# schema_carte_mere.net
KiCad netlist of a schematic drawn in EAGLE
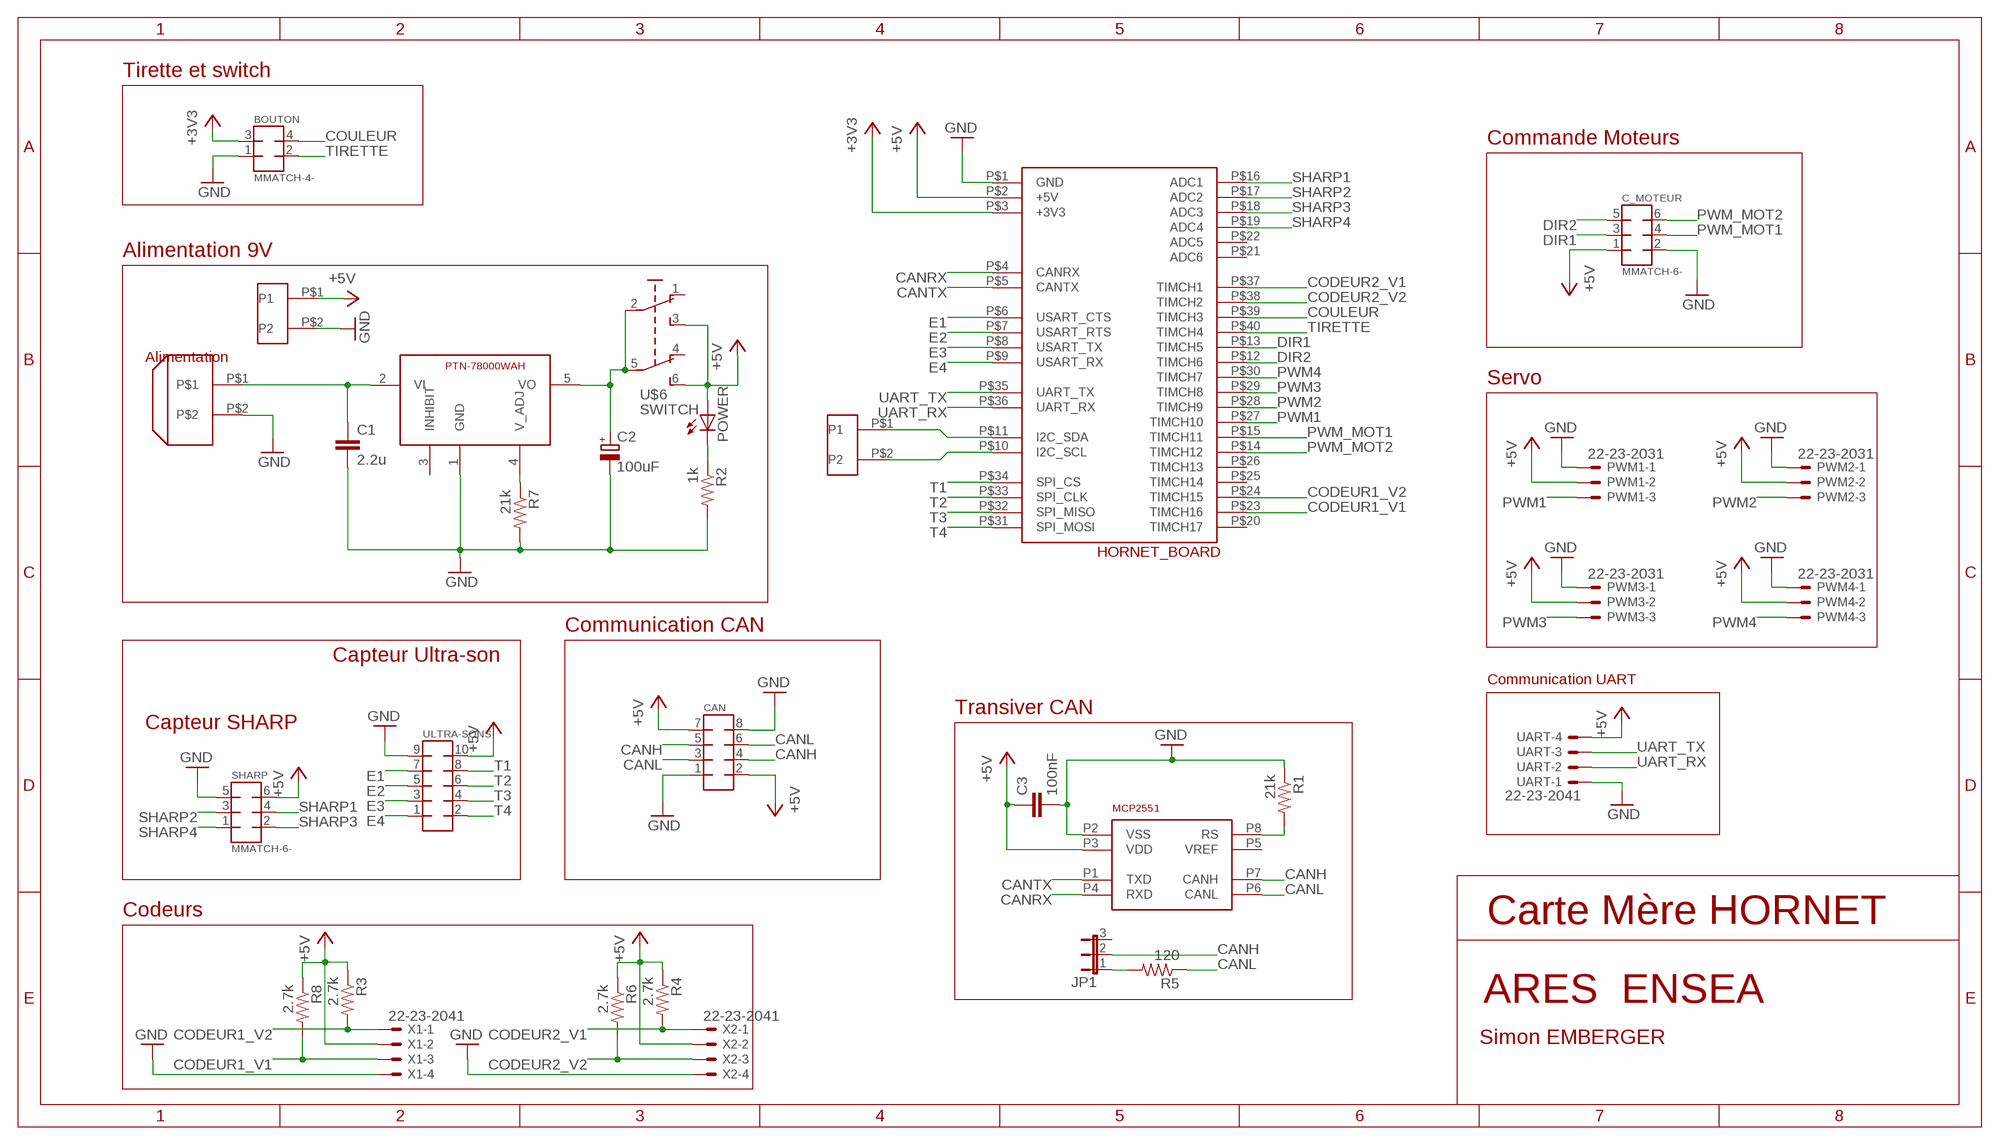
[diagram p0: schematic, sheet 1]

(export (version "E")
  (design (tool "Eeschema 10.0.6"))
  (components
    (comp (ref "ALIM")
      (value "PM5.08_2")
      (footprint "eagle-import:PM5.08_2")
      (libsource (lib "eagle-import") (part "PM5.08_2"))
    )
    (comp (ref "BOUTON")
      (value "MMATCH-4-")
      (footprint "eagle-import:AMP-215079-4")
      (libsource (lib "eagle-import") (part "MMATCH-4-"))
    )
    (comp (ref "C1")
      (value "2.2u")
      (footprint "eagle-import:C1210")
      (libsource (lib "eagle-import") (part "C-EUC1210"))
    )
    (comp (ref "C2")
      (value "100uF")
      (footprint "eagle-import:153CLV-0807")
      (libsource (lib "eagle-import") (part "CPOL-EU153CLV-0807"))
    )
    (comp (ref "C3")
      (value "100nF")
      (footprint "eagle-import:C0805")
      (libsource (lib "eagle-import") (part "C-EUC0805"))
    )
    (comp (ref "CAN")
      (value "MMATCH-8-PTH")
      (footprint "eagle-import:AMP-215079-8")
      (libsource (lib "eagle-import") (part "MMATCH-8-PTH"))
    )
    (comp (ref "C_MOTEUR")
      (value "MMATCH-6-")
      (footprint "eagle-import:AMP-215079-6")
      (libsource (lib "eagle-import") (part "MMATCH-6-"))
    )
    (comp (ref "JP1")
      (value "JP2W")
      (footprint "eagle-import:JP2W")
      (libsource (lib "eagle-import") (part "JP2W"))
    )
    (comp (ref "PIN_ALIM")
      (value "2_PIN")
      (footprint "eagle-import:2_PIN")
      (libsource (lib "eagle-import") (part "2_PIN"))
    )
    (comp (ref "POWER")
      (value "LEDCHIPLED_0805")
      (footprint "eagle-import:CHIPLED_0805")
      (libsource (lib "eagle-import") (part "LEDCHIPLED_0805"))
    )
    (comp (ref "PWM1")
      (value "22-23-2031")
      (footprint "eagle-import:22-23-2031")
      (fields (field (name "MF") "MOLEX"))
      (libsource (lib "eagle-import") (part "22-23-2031"))
    )
    (comp (ref "PWM2")
      (value "22-23-2031")
      (footprint "eagle-import:22-23-2031")
      (fields (field (name "MF") "MOLEX"))
      (libsource (lib "eagle-import") (part "22-23-2031"))
    )
    (comp (ref "PWM3")
      (value "22-23-2031")
      (footprint "eagle-import:22-23-2031")
      (fields (field (name "MF") "MOLEX"))
      (libsource (lib "eagle-import") (part "22-23-2031"))
    )
    (comp (ref "PWM4")
      (value "22-23-2031")
      (footprint "eagle-import:22-23-2031")
      (fields (field (name "MF") "MOLEX"))
      (libsource (lib "eagle-import") (part "22-23-2031"))
    )
    (comp (ref "R1")
      (value "21k")
      (footprint "eagle-import:M0805")
      (libsource (lib "eagle-import") (part "R-US_M0805"))
    )
    (comp (ref "R2")
      (value "1k")
      (footprint "eagle-import:M0805")
      (libsource (lib "eagle-import") (part "R-US_M0805"))
    )
    (comp (ref "R3")
      (value "2.7k")
      (footprint "eagle-import:M0805")
      (libsource (lib "eagle-import") (part "R-US_M0805"))
    )
    (comp (ref "R4")
      (value "2.7k")
      (footprint "eagle-import:M0805")
      (libsource (lib "eagle-import") (part "R-US_M0805"))
    )
    (comp (ref "R5")
      (value "120")
      (footprint "eagle-import:M0805")
      (libsource (lib "eagle-import") (part "R-US_M0805"))
    )
    (comp (ref "R6")
      (value "2.7k")
      (footprint "eagle-import:M0805")
      (libsource (lib "eagle-import") (part "R-US_M0805"))
    )
    (comp (ref "R7")
      (value "21k")
      (footprint "eagle-import:M0805")
      (libsource (lib "eagle-import") (part "R-US_M0805"))
    )
    (comp (ref "R8")
      (value "2.7k")
      (footprint "eagle-import:M0805")
      (libsource (lib "eagle-import") (part "R-US_M0805"))
    )
    (comp (ref "SHARP")
      (value "MMATCH-6-")
      (footprint "eagle-import:AMP-215079-6")
      (libsource (lib "eagle-import") (part "MMATCH-6-"))
    )
    (comp (ref "U$1")
      (value "HORNET_BOARD")
      (footprint "eagle-import:HORNET_EXT_20")
      (libsource (lib "eagle-import") (part "HORNET_BOARD"))
    )
    (comp (ref "U$2")
      (value "MCP2551")
      (footprint "eagle-import:SOIC_8")
      (libsource (lib "eagle-import") (part "MCP2551"))
    )
    (comp (ref "U$3")
      (value "2_PIN")
      (footprint "eagle-import:2_PIN")
      (libsource (lib "eagle-import") (part "2_PIN"))
    )
    (comp (ref "U$6")
      (value "SWITCH")
      (footprint "eagle-import:SWITCH")
      (libsource (lib "eagle-import") (part "SWITCH"))
    )
    (comp (ref "U$18")
      (value "PTN-78000WAH")
      (footprint "eagle-import:PCK-PTN-78000WAH")
      (libsource (lib "eagle-import") (part "PTN-78000WAH"))
    )
    (comp (ref "UART")
      (value "22-23-2041")
      (footprint "eagle-import:22-23-2041")
      (fields (field (name "MF") "MOLEX"))
      (libsource (lib "eagle-import") (part "22-23-2041"))
    )
    (comp (ref "ULTRA-SONS")
      (value "MMATCH-10-PTH")
      (footprint "eagle-import:AMP-215079-10")
      (libsource (lib "eagle-import") (part "MMATCH-10-PTH"))
    )
    (comp (ref "X1")
      (value "22-23-2041")
      (footprint "eagle-import:22-23-2041")
      (fields (field (name "MF") "MOLEX"))
      (libsource (lib "eagle-import") (part "22-23-2041"))
    )
    (comp (ref "X2")
      (value "22-23-2041")
      (footprint "eagle-import:22-23-2041")
      (fields (field (name "MF") "MOLEX"))
      (libsource (lib "eagle-import") (part "22-23-2041"))
    )
  )
  (nets
    (net (code "1") (name "+3V3") (class "Default")
      (node (ref "BOUTON") (pin "3") (pinfunction "7_3") (pintype "bidirectional"))
      (node (ref "U$1") (pin "P$3") (pinfunction "+3V3_P$3") (pintype "bidirectional"))
    )
    (net (code "2") (name "+5V") (class "Default")
      (node (ref "C3") (pin "1") (pinfunction "1_1") (pintype "passive"))
      (node (ref "CAN") (pin "2") (pinfunction "2_2") (pintype "bidirectional"))
      (node (ref "CAN") (pin "7") (pinfunction "7_7") (pintype "bidirectional"))
      (node (ref "C_MOTEUR") (pin "1") (pinfunction "3_1") (pintype "bidirectional"))
      (node (ref "PIN_ALIM") (pin "P$1") (pinfunction "P1_P$1") (pintype "bidirectional"))
      (node (ref "POWER") (pin "A") (pinfunction "A_A") (pintype "passive"))
      (node (ref "PWM1") (pin "2") (pinfunction "S_2") (pintype "passive"))
      (node (ref "PWM2") (pin "2") (pinfunction "S_2") (pintype "passive"))
      (node (ref "PWM3") (pin "2") (pinfunction "S_2") (pintype "passive"))
      (node (ref "PWM4") (pin "2") (pinfunction "S_2") (pintype "passive"))
      (node (ref "R3") (pin "1") (pinfunction "1_1") (pintype "passive"))
      (node (ref "R4") (pin "1") (pinfunction "1_1") (pintype "passive"))
      (node (ref "R6") (pin "1") (pinfunction "1_1") (pintype "passive"))
      (node (ref "R8") (pin "1") (pinfunction "1_1") (pintype "passive"))
      (node (ref "SHARP") (pin "6") (pinfunction "8_6") (pintype "bidirectional"))
      (node (ref "U$1") (pin "P$2") (pinfunction "+5V_P$2") (pintype "bidirectional"))
      (node (ref "U$2") (pin "P3") (pinfunction "VDD_P3") (pintype "bidirectional"))
      (node (ref "U$6") (pin "3") (pinfunction "S_3") (pintype "passive"))
      (node (ref "U$6") (pin "6") (pinfunction "S1_6") (pintype "passive"))
      (node (ref "UART") (pin "4") (pinfunction "S_4") (pintype "passive"))
      (node (ref "ULTRA-SONS") (pin "10") (pinfunction "10_10") (pintype "bidirectional"))
      (node (ref "X1") (pin "2") (pinfunction "S_2") (pintype "passive"))
      (node (ref "X2") (pin "2") (pinfunction "S_2") (pintype "passive"))
    )
    (net (code "3") (name "/CANH") (class "Default")
      (node (ref "CAN") (pin "4") (pinfunction "4_4") (pintype "bidirectional"))
      (node (ref "CAN") (pin "5") (pinfunction "5_5") (pintype "bidirectional"))
      (node (ref "JP1") (pin "2") (pinfunction "2_2") (pintype "passive"))
      (node (ref "U$2") (pin "P7") (pinfunction "CANH_P7") (pintype "bidirectional"))
    )
    (net (code "4") (name "/CANL") (class "Default")
      (node (ref "CAN") (pin "3") (pinfunction "3_3") (pintype "bidirectional"))
      (node (ref "CAN") (pin "6") (pinfunction "6_6") (pintype "bidirectional"))
      (node (ref "R5") (pin "1") (pinfunction "1_1") (pintype "passive"))
      (node (ref "U$2") (pin "P6") (pinfunction "CANL_P6") (pintype "bidirectional"))
    )
    (net (code "5") (name "/CANRX") (class "Default")
      (node (ref "U$1") (pin "P$4") (pinfunction "CANRX_P$4") (pintype "bidirectional"))
      (node (ref "U$2") (pin "P4") (pinfunction "RXD_P4") (pintype "bidirectional"))
    )
    (net (code "6") (name "/CANTX") (class "Default")
      (node (ref "U$1") (pin "P$5") (pinfunction "CANTX_P$5") (pintype "bidirectional"))
      (node (ref "U$2") (pin "P1") (pinfunction "TXD_P1") (pintype "bidirectional"))
    )
    (net (code "7") (name "/CODEUR1_V1") (class "Default")
      (node (ref "R8") (pin "2") (pinfunction "2_2") (pintype "passive"))
      (node (ref "U$1") (pin "P$23") (pinfunction "TIMCH16_P$23") (pintype "bidirectional"))
      (node (ref "X1") (pin "3") (pinfunction "S_3") (pintype "passive"))
    )
    (net (code "8") (name "/CODEUR1_V2") (class "Default")
      (node (ref "R3") (pin "2") (pinfunction "2_2") (pintype "passive"))
      (node (ref "U$1") (pin "P$24") (pinfunction "TIMCH15_P$24") (pintype "bidirectional"))
      (node (ref "X1") (pin "1") (pinfunction "S_1") (pintype "passive"))
    )
    (net (code "9") (name "/CODEUR2_V1") (class "Default")
      (node (ref "R4") (pin "2") (pinfunction "2_2") (pintype "passive"))
      (node (ref "U$1") (pin "P$37") (pinfunction "TIMCH1_P$37") (pintype "bidirectional"))
      (node (ref "X2") (pin "1") (pinfunction "S_1") (pintype "passive"))
    )
    (net (code "10") (name "/CODEUR2_V2") (class "Default")
      (node (ref "R6") (pin "2") (pinfunction "2_2") (pintype "passive"))
      (node (ref "U$1") (pin "P$38") (pinfunction "TIMCH2_P$38") (pintype "bidirectional"))
      (node (ref "X2") (pin "3") (pinfunction "S_3") (pintype "passive"))
    )
    (net (code "11") (name "/COULEUR") (class "Default")
      (node (ref "BOUTON") (pin "4") (pinfunction "8_4") (pintype "bidirectional"))
      (node (ref "U$1") (pin "P$39") (pinfunction "TIMCH3_P$39") (pintype "bidirectional"))
    )
    (net (code "12") (name "/DIR1") (class "Default")
      (node (ref "C_MOTEUR") (pin "3") (pinfunction "5_3") (pintype "bidirectional"))
      (node (ref "U$1") (pin "P$13") (pinfunction "TIMCH5_P$13") (pintype "bidirectional"))
    )
    (net (code "13") (name "/DIR2") (class "Default")
      (node (ref "C_MOTEUR") (pin "5") (pinfunction "7_5") (pintype "bidirectional"))
      (node (ref "U$1") (pin "P$12") (pinfunction "TIMCH6_P$12") (pintype "bidirectional"))
    )
    (net (code "14") (name "/E1") (class "Default")
      (node (ref "U$1") (pin "P$6") (pinfunction "USART_CTS_P$6") (pintype "bidirectional"))
      (node (ref "ULTRA-SONS") (pin "7") (pinfunction "7_7") (pintype "bidirectional"))
    )
    (net (code "15") (name "/E2") (class "Default")
      (node (ref "U$1") (pin "P$7") (pinfunction "USART_RTS_P$7") (pintype "bidirectional"))
      (node (ref "ULTRA-SONS") (pin "5") (pinfunction "5_5") (pintype "bidirectional"))
    )
    (net (code "16") (name "/E3") (class "Default")
      (node (ref "U$1") (pin "P$8") (pinfunction "USART_TX_P$8") (pintype "bidirectional"))
      (node (ref "ULTRA-SONS") (pin "3") (pinfunction "3_3") (pintype "bidirectional"))
    )
    (net (code "17") (name "/E4") (class "Default")
      (node (ref "U$1") (pin "P$9") (pinfunction "USART_RX_P$9") (pintype "bidirectional"))
      (node (ref "ULTRA-SONS") (pin "1") (pinfunction "1_1") (pintype "bidirectional"))
    )
    (net (code "18") (name "/PWM1") (class "Default")
      (node (ref "PWM1") (pin "3") (pinfunction "S_3") (pintype "passive"))
      (node (ref "U$1") (pin "P$27") (pinfunction "TIMCH10_P$27") (pintype "bidirectional"))
    )
    (net (code "19") (name "/PWM2") (class "Default")
      (node (ref "PWM2") (pin "3") (pinfunction "S_3") (pintype "passive"))
      (node (ref "U$1") (pin "P$28") (pinfunction "TIMCH9_P$28") (pintype "bidirectional"))
    )
    (net (code "20") (name "/PWM3") (class "Default")
      (node (ref "PWM3") (pin "3") (pinfunction "S_3") (pintype "passive"))
      (node (ref "U$1") (pin "P$29") (pinfunction "TIMCH8_P$29") (pintype "bidirectional"))
    )
    (net (code "21") (name "/PWM4") (class "Default")
      (node (ref "PWM4") (pin "3") (pinfunction "S_3") (pintype "passive"))
      (node (ref "U$1") (pin "P$30") (pinfunction "TIMCH7_P$30") (pintype "bidirectional"))
    )
    (net (code "22") (name "/PWM_MOT1") (class "Default")
      (node (ref "C_MOTEUR") (pin "4") (pinfunction "6_4") (pintype "bidirectional"))
      (node (ref "U$1") (pin "P$15") (pinfunction "TIMCH11_P$15") (pintype "bidirectional"))
    )
    (net (code "23") (name "/PWM_MOT2") (class "Default")
      (node (ref "C_MOTEUR") (pin "6") (pinfunction "8_6") (pintype "bidirectional"))
      (node (ref "U$1") (pin "P$14") (pinfunction "TIMCH12_P$14") (pintype "bidirectional"))
    )
    (net (code "24") (name "/SHARP1") (class "Default")
      (node (ref "SHARP") (pin "4") (pinfunction "6_4") (pintype "bidirectional"))
      (node (ref "U$1") (pin "P$16") (pinfunction "ADC1_P$16") (pintype "bidirectional"))
    )
    (net (code "25") (name "/SHARP2") (class "Default")
      (node (ref "SHARP") (pin "3") (pinfunction "5_3") (pintype "bidirectional"))
      (node (ref "U$1") (pin "P$17") (pinfunction "ADC2_P$17") (pintype "bidirectional"))
    )
    (net (code "26") (name "/SHARP3") (class "Default")
      (node (ref "SHARP") (pin "2") (pinfunction "4_2") (pintype "bidirectional"))
      (node (ref "U$1") (pin "P$18") (pinfunction "ADC3_P$18") (pintype "bidirectional"))
    )
    (net (code "27") (name "/SHARP4") (class "Default")
      (node (ref "SHARP") (pin "1") (pinfunction "3_1") (pintype "bidirectional"))
      (node (ref "U$1") (pin "P$19") (pinfunction "ADC4_P$19") (pintype "bidirectional"))
    )
    (net (code "28") (name "/T1") (class "Default")
      (node (ref "U$1") (pin "P$34") (pinfunction "SPI_CS_P$34") (pintype "bidirectional"))
      (node (ref "ULTRA-SONS") (pin "8") (pinfunction "8_8") (pintype "bidirectional"))
    )
    (net (code "29") (name "/T2") (class "Default")
      (node (ref "U$1") (pin "P$33") (pinfunction "SPI_CLK_P$33") (pintype "bidirectional"))
      (node (ref "ULTRA-SONS") (pin "6") (pinfunction "6_6") (pintype "bidirectional"))
    )
    (net (code "30") (name "/T3") (class "Default")
      (node (ref "U$1") (pin "P$32") (pinfunction "SPI_MISO_P$32") (pintype "bidirectional"))
      (node (ref "ULTRA-SONS") (pin "4") (pinfunction "4_4") (pintype "bidirectional"))
    )
    (net (code "31") (name "/T4") (class "Default")
      (node (ref "U$1") (pin "P$31") (pinfunction "SPI_MOSI_P$31") (pintype "bidirectional"))
      (node (ref "ULTRA-SONS") (pin "2") (pinfunction "2_2") (pintype "bidirectional"))
    )
    (net (code "32") (name "/TIRETTE") (class "Default")
      (node (ref "BOUTON") (pin "2") (pinfunction "6_2") (pintype "bidirectional"))
      (node (ref "U$1") (pin "P$40") (pinfunction "TIMCH4_P$40") (pintype "bidirectional"))
    )
    (net (code "33") (name "/UART_RX") (class "Default")
      (node (ref "U$1") (pin "P$36") (pinfunction "UART_RX_P$36") (pintype "bidirectional"))
      (node (ref "UART") (pin "2") (pinfunction "S_2") (pintype "passive"))
    )
    (net (code "34") (name "/UART_TX") (class "Default")
      (node (ref "U$1") (pin "P$35") (pinfunction "UART_TX_P$35") (pintype "bidirectional"))
      (node (ref "UART") (pin "3") (pinfunction "S_3") (pintype "passive"))
    )
    (net (code "35") (name "GND") (class "Default")
      (node (ref "ALIM") (pin "P$2") (pinfunction "P$2_P$2") (pintype "bidirectional"))
      (node (ref "BOUTON") (pin "1") (pinfunction "5_1") (pintype "bidirectional"))
      (node (ref "C1") (pin "2") (pinfunction "2_2") (pintype "passive"))
      (node (ref "C2") (pin "-") (pinfunction "-_-") (pintype "passive"))
      (node (ref "C3") (pin "2") (pinfunction "2_2") (pintype "passive"))
      (node (ref "CAN") (pin "1") (pinfunction "1_1") (pintype "bidirectional"))
      (node (ref "CAN") (pin "8") (pinfunction "8_8") (pintype "bidirectional"))
      (node (ref "C_MOTEUR") (pin "2") (pinfunction "4_2") (pintype "bidirectional"))
      (node (ref "PIN_ALIM") (pin "P$2") (pinfunction "P2_P$2") (pintype "bidirectional"))
      (node (ref "PWM1") (pin "1") (pinfunction "S_1") (pintype "passive"))
      (node (ref "PWM2") (pin "1") (pinfunction "S_1") (pintype "passive"))
      (node (ref "PWM3") (pin "1") (pinfunction "S_1") (pintype "passive"))
      (node (ref "PWM4") (pin "1") (pinfunction "S_1") (pintype "passive"))
      (node (ref "R1") (pin "1") (pinfunction "1_1") (pintype "passive"))
      (node (ref "R2") (pin "2") (pinfunction "2_2") (pintype "passive"))
      (node (ref "R7") (pin "2") (pinfunction "2_2") (pintype "passive"))
      (node (ref "SHARP") (pin "5") (pinfunction "7_5") (pintype "bidirectional"))
      (node (ref "U$1") (pin "P$1") (pinfunction "GND_P$1") (pintype "bidirectional"))
      (node (ref "U$18") (pin "1") (pinfunction "GND_1") (pintype "bidirectional"))
      (node (ref "U$2") (pin "P2") (pinfunction "VSS_P2") (pintype "bidirectional"))
      (node (ref "UART") (pin "1") (pinfunction "S_1") (pintype "passive"))
      (node (ref "ULTRA-SONS") (pin "9") (pinfunction "9_9") (pintype "bidirectional"))
      (node (ref "X1") (pin "4") (pinfunction "S_4") (pintype "passive"))
      (node (ref "X2") (pin "4") (pinfunction "S_4") (pintype "passive"))
    )
    (net (code "36") (name "Net-(JP1-Pad1)") (class "Default")
      (node (ref "JP1") (pin "1") (pinfunction "1_1") (pintype "passive"))
      (node (ref "R5") (pin "2") (pinfunction "2_2") (pintype "passive"))
    )
    (net (code "37") (name "Net-(POWER-PadC)") (class "Default")
      (node (ref "POWER") (pin "C") (pinfunction "C_C") (pintype "passive"))
      (node (ref "R2") (pin "1") (pinfunction "1_1") (pintype "passive"))
    )
    (net (code "38") (name "Net-(U$1-I2C_SCL)") (class "Default")
      (node (ref "U$1") (pin "P$10") (pinfunction "I2C_SCL_P$10") (pintype "bidirectional"))
      (node (ref "U$3") (pin "P$2") (pinfunction "P2_P$2") (pintype "bidirectional"))
    )
    (net (code "39") (name "Net-(U$1-I2C_SDA)") (class "Default")
      (node (ref "U$1") (pin "P$11") (pinfunction "I2C_SDA_P$11") (pintype "bidirectional"))
      (node (ref "U$3") (pin "P$1") (pinfunction "P1_P$1") (pintype "bidirectional"))
    )
    (net (code "40") (name "Net-(U$2-RS)") (class "Default")
      (node (ref "R1") (pin "2") (pinfunction "2_2") (pintype "passive"))
      (node (ref "U$2") (pin "P8") (pinfunction "RS_P8") (pintype "bidirectional"))
    )
    (net (code "41") (name "Net-(U$18-VI)") (class "Default")
      (node (ref "ALIM") (pin "P$1") (pinfunction "P$1_P$1") (pintype "bidirectional"))
      (node (ref "C1") (pin "1") (pinfunction "1_1") (pintype "passive"))
      (node (ref "U$18") (pin "2") (pinfunction "VI_2") (pintype "bidirectional"))
    )
    (net (code "42") (name "Net-(U$18-VO)") (class "Default")
      (node (ref "C2") (pin "+") (pinfunction "+_+") (pintype "passive"))
      (node (ref "U$18") (pin "5") (pinfunction "VO_5") (pintype "bidirectional"))
      (node (ref "U$6") (pin "2") (pinfunction "P_2") (pintype "passive"))
      (node (ref "U$6") (pin "5") (pinfunction "P1_5") (pintype "passive"))
    )
    (net (code "43") (name "Net-(U$18-V_ADJ)") (class "Default")
      (node (ref "R7") (pin "1") (pinfunction "1_1") (pintype "passive"))
      (node (ref "U$18") (pin "4") (pinfunction "V_ADJ_4") (pintype "bidirectional"))
    )
    (net (code "44") (name "unconnected-(JP1-Pad3)") (class "Default")
      (node (ref "JP1") (pin "3") (pinfunction "3_3") (pintype "passive"))
    )
    (net (code "45") (name "unconnected-(U$1-ADC5-PadP$22)") (class "Default")
      (node (ref "U$1") (pin "P$22") (pinfunction "ADC5_P$22") (pintype "bidirectional"))
    )
    (net (code "46") (name "unconnected-(U$1-ADC6-PadP$21)") (class "Default")
      (node (ref "U$1") (pin "P$21") (pinfunction "ADC6_P$21") (pintype "bidirectional"))
    )
    (net (code "47") (name "unconnected-(U$1-TIMCH13-PadP$26)") (class "Default")
      (node (ref "U$1") (pin "P$26") (pinfunction "TIMCH13_P$26") (pintype "bidirectional"))
    )
    (net (code "48") (name "unconnected-(U$1-TIMCH14-PadP$25)") (class "Default")
      (node (ref "U$1") (pin "P$25") (pinfunction "TIMCH14_P$25") (pintype "bidirectional"))
    )
    (net (code "49") (name "unconnected-(U$1-TIMCH17-PadP$20)") (class "Default")
      (node (ref "U$1") (pin "P$20") (pinfunction "TIMCH17_P$20") (pintype "bidirectional"))
    )
    (net (code "50") (name "unconnected-(U$2-VREF-PadP5)") (class "Default")
      (node (ref "U$2") (pin "P5") (pinfunction "VREF_P5") (pintype "bidirectional"))
    )
    (net (code "51") (name "unconnected-(U$6-O-Pad1)") (class "Default")
      (node (ref "U$6") (pin "1") (pinfunction "O_1") (pintype "passive"))
    )
    (net (code "52") (name "unconnected-(U$6-O1-Pad4)") (class "Default")
      (node (ref "U$6") (pin "4") (pinfunction "O1_4") (pintype "passive"))
    )
    (net (code "53") (name "unconnected-(U$18-INHIBIT-Pad3)") (class "Default")
      (node (ref "U$18") (pin "3") (pinfunction "INHIBIT_3") (pintype "bidirectional"))
    )
  )
)
